# Chap-11-3.net
KiCad netlist of a schematic drawn in Altium Designer
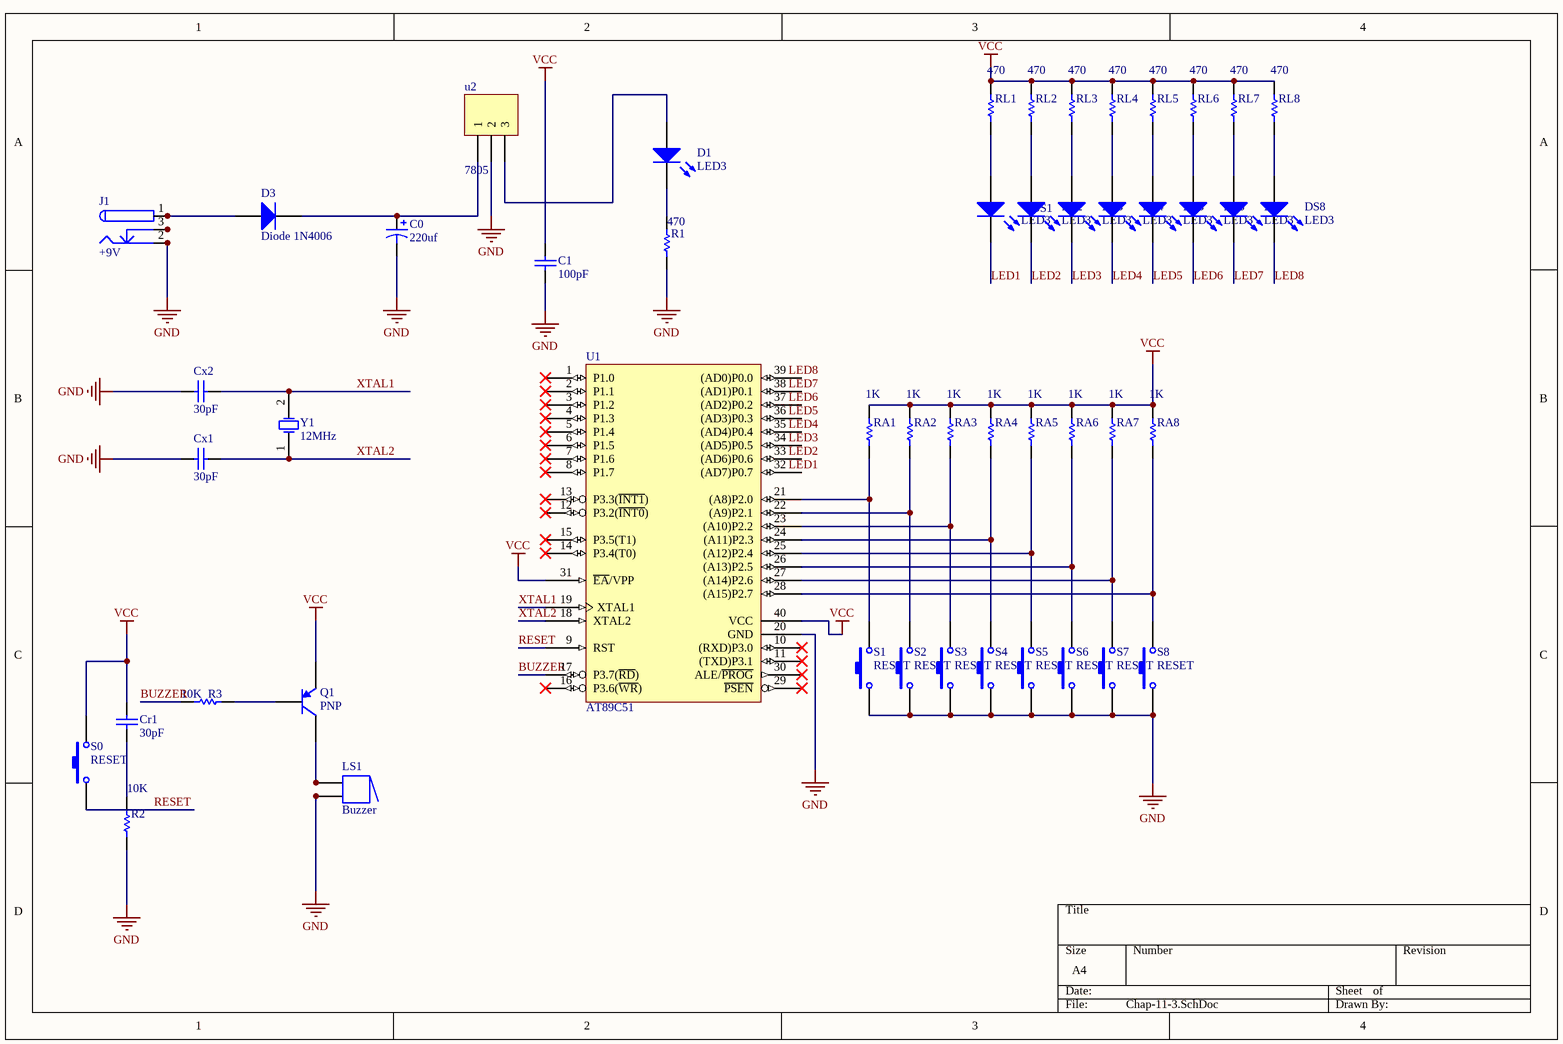
[diagram p0: Chap-11-3.SchDoc]

(export (version "E")
  (design (tool "Eeschema 10.0.6"))
  (components
    (comp (ref "C0")
      (value "220uf")
      (footprint "RB7.6-15")
      (description "Polarized Capacitor (Radial)")
      (fields (field (name "Comment") "Cap Pol1") (field (name "PUBLISHER") "Altium Limited"))
      (libsource (lib "Chap-11-实践题(3)") (part "Cap Pol1"))
    )
    (comp (ref "C1")
      (value "100pF")
      (footprint "RAD-0.3")
      (description "Capacitor")
      (fields (field (name "Comment") "Cap") (field (name "PUBLISHER") "Altium Limited"))
      (libsource (lib "Chap-11-实践题(3)") (part "Cap"))
    )
    (comp (ref "Cr1")
      (value "30pF")
      (footprint "RAD-0.3")
      (description "Capacitor")
      (fields (field (name "Comment") "Cap") (field (name "PUBLISHER") "Altium Limited"))
      (libsource (lib "Chap-11-实践题(3)") (part "Cap"))
    )
    (comp (ref "Cx1")
      (value "30pF")
      (footprint "RAD-0.3")
      (description "Capacitor")
      (fields (field (name "Comment") "Cap") (field (name "PUBLISHER") "Altium Limited"))
      (libsource (lib "Chap-11-实践题(3)") (part "Cap"))
    )
    (comp (ref "Cx2")
      (value "30pF")
      (footprint "RAD-0.3")
      (description "Capacitor")
      (fields (field (name "Comment") "Cap") (field (name "PUBLISHER") "Altium Limited"))
      (libsource (lib "Chap-11-实践题(3)") (part "Cap"))
    )
    (comp (ref "D1")
      (value "LED3")
      (footprint "3.5X2.8X1.9")
      (description "Typical BLUE SiC LED")
      (fields (field (name "PUBLISHER") "Altium Limited"))
      (libsource (lib "Chap-11-实践题(3)") (part "LED3"))
    )
    (comp (ref "D3")
      (value "Diode 1N4006")
      (footprint "DO-41")
      (description "1 Amp General Purpose Rectifier")
      (fields (field (name "PUBLISHER") "Altium Limited"))
      (libsource (lib "Chap-11-实践题(3)") (part "Diode 1N4006"))
    )
    (comp (ref "DS1")
      (value "LED3")
      (footprint "3.5X2.8X1.9")
      (description "Typical BLUE SiC LED")
      (fields (field (name "PUBLISHER") "Altium Limited"))
      (libsource (lib "Chap-11-实践题(3)") (part "LED3"))
    )
    (comp (ref "DS2")
      (value "LED3")
      (footprint "3.5X2.8X1.9")
      (description "Typical BLUE SiC LED")
      (fields (field (name "PUBLISHER") "Altium Limited"))
      (libsource (lib "Chap-11-实践题(3)") (part "LED3"))
    )
    (comp (ref "DS3")
      (value "LED3")
      (footprint "3.5X2.8X1.9")
      (description "Typical BLUE SiC LED")
      (fields (field (name "PUBLISHER") "Altium Limited"))
      (libsource (lib "Chap-11-实践题(3)") (part "LED3"))
    )
    (comp (ref "DS4")
      (value "LED3")
      (footprint "3.5X2.8X1.9")
      (description "Typical BLUE SiC LED")
      (fields (field (name "PUBLISHER") "Altium Limited"))
      (libsource (lib "Chap-11-实践题(3)") (part "LED3"))
    )
    (comp (ref "DS5")
      (value "LED3")
      (footprint "3.5X2.8X1.9")
      (description "Typical BLUE SiC LED")
      (fields (field (name "PUBLISHER") "Altium Limited"))
      (libsource (lib "Chap-11-实践题(3)") (part "LED3"))
    )
    (comp (ref "DS6")
      (value "LED3")
      (footprint "3.5X2.8X1.9")
      (description "Typical BLUE SiC LED")
      (fields (field (name "PUBLISHER") "Altium Limited"))
      (libsource (lib "Chap-11-实践题(3)") (part "LED3"))
    )
    (comp (ref "DS7")
      (value "LED3")
      (footprint "3.5X2.8X1.9")
      (description "Typical BLUE SiC LED")
      (fields (field (name "PUBLISHER") "Altium Limited"))
      (libsource (lib "Chap-11-实践题(3)") (part "LED3"))
    )
    (comp (ref "DS8")
      (value "LED3")
      (footprint "3.5X2.8X1.9")
      (description "Typical BLUE SiC LED")
      (fields (field (name "PUBLISHER") "Altium Limited"))
      (libsource (lib "Chap-11-实践题(3)") (part "LED3"))
    )
    (comp (ref "J1")
      (value "+9V")
      (footprint "KLD-0202")
      (description "Low Voltage Power Supply Connector")
      (fields (field (name "PUBLISHER") "Altium Limited"))
      (libsource (lib "Chap-11-实践题(3)") (part "PWR2.5"))
    )
    (comp (ref "LS1")
      (value "Buzzer")
      (footprint "ABSM-1574")
      (description "Magnetic Transducer Buzzer")
      (fields (field (name "PUBLISHER") "Altium Limited"))
      (libsource (lib "Chap-11-实践题(3)") (part "Buzzer"))
    )
    (comp (ref "Q1")
      (value "PNP")
      (footprint "TO-92A")
      (description "PNP General Purpose Amplifier")
      (fields (field (name "PUBLISHER") "Altium Limited"))
      (libsource (lib "Chap-11-实践题(3)") (part "2N3906"))
    )
    (comp (ref "R1")
      (value "470")
      (footprint "AXIAL-0.3")
      (description "Resistor")
      (fields (field (name "Comment") "Res1") (field (name "PUBLISHER") "Altium Limited"))
      (libsource (lib "Chap-11-实践题(3)") (part "Res1"))
    )
    (comp (ref "R2")
      (value "10K")
      (footprint "AXIAL-0.3")
      (description "Resistor")
      (fields (field (name "Comment") "Res1") (field (name "PUBLISHER") "Altium Limited"))
      (libsource (lib "Chap-11-实践题(3)") (part "Res1"))
    )
    (comp (ref "R3")
      (value "10K")
      (footprint "AXIAL-0.3")
      (description "Resistor")
      (fields (field (name "Comment") "Res1") (field (name "PUBLISHER") "Altium Limited"))
      (libsource (lib "Chap-11-实践题(3)") (part "Res1"))
    )
    (comp (ref "RA1")
      (value "1K")
      (footprint "AXIAL-0.3")
      (description "Resistor")
      (fields (field (name "Comment") "Res1") (field (name "PUBLISHER") "Altium Limited"))
      (libsource (lib "Chap-11-实践题(3)") (part "Res1"))
    )
    (comp (ref "RA2")
      (value "1K")
      (footprint "AXIAL-0.3")
      (description "Resistor")
      (fields (field (name "Comment") "Res1") (field (name "PUBLISHER") "Altium Limited"))
      (libsource (lib "Chap-11-实践题(3)") (part "Res1"))
    )
    (comp (ref "RA3")
      (value "1K")
      (footprint "AXIAL-0.3")
      (description "Resistor")
      (fields (field (name "Comment") "Res1") (field (name "PUBLISHER") "Altium Limited"))
      (libsource (lib "Chap-11-实践题(3)") (part "Res1"))
    )
    (comp (ref "RA4")
      (value "1K")
      (footprint "AXIAL-0.3")
      (description "Resistor")
      (fields (field (name "Comment") "Res1") (field (name "PUBLISHER") "Altium Limited"))
      (libsource (lib "Chap-11-实践题(3)") (part "Res1"))
    )
    (comp (ref "RA5")
      (value "1K")
      (footprint "AXIAL-0.3")
      (description "Resistor")
      (fields (field (name "Comment") "Res1") (field (name "PUBLISHER") "Altium Limited"))
      (libsource (lib "Chap-11-实践题(3)") (part "Res1"))
    )
    (comp (ref "RA6")
      (value "1K")
      (footprint "AXIAL-0.3")
      (description "Resistor")
      (fields (field (name "Comment") "Res1") (field (name "PUBLISHER") "Altium Limited"))
      (libsource (lib "Chap-11-实践题(3)") (part "Res1"))
    )
    (comp (ref "RA7")
      (value "1K")
      (footprint "AXIAL-0.3")
      (description "Resistor")
      (fields (field (name "Comment") "Res1") (field (name "PUBLISHER") "Altium Limited"))
      (libsource (lib "Chap-11-实践题(3)") (part "Res1"))
    )
    (comp (ref "RA8")
      (value "1K")
      (footprint "AXIAL-0.3")
      (description "Resistor")
      (fields (field (name "Comment") "Res1") (field (name "PUBLISHER") "Altium Limited"))
      (libsource (lib "Chap-11-实践题(3)") (part "Res1"))
    )
    (comp (ref "RL1")
      (value "470")
      (footprint "AXIAL-0.3")
      (description "Resistor")
      (fields (field (name "Comment") "Res1") (field (name "PUBLISHER") "Altium Limited"))
      (libsource (lib "Chap-11-实践题(3)") (part "Res1"))
    )
    (comp (ref "RL2")
      (value "470")
      (footprint "AXIAL-0.3")
      (description "Resistor")
      (fields (field (name "Comment") "Res1") (field (name "PUBLISHER") "Altium Limited"))
      (libsource (lib "Chap-11-实践题(3)") (part "Res1"))
    )
    (comp (ref "RL3")
      (value "470")
      (footprint "AXIAL-0.3")
      (description "Resistor")
      (fields (field (name "Comment") "Res1") (field (name "PUBLISHER") "Altium Limited"))
      (libsource (lib "Chap-11-实践题(3)") (part "Res1"))
    )
    (comp (ref "RL4")
      (value "470")
      (footprint "AXIAL-0.3")
      (description "Resistor")
      (fields (field (name "Comment") "Res1") (field (name "PUBLISHER") "Altium Limited"))
      (libsource (lib "Chap-11-实践题(3)") (part "Res1"))
    )
    (comp (ref "RL5")
      (value "470")
      (footprint "AXIAL-0.3")
      (description "Resistor")
      (fields (field (name "Comment") "Res1") (field (name "PUBLISHER") "Altium Limited"))
      (libsource (lib "Chap-11-实践题(3)") (part "Res1"))
    )
    (comp (ref "RL6")
      (value "470")
      (footprint "AXIAL-0.3")
      (description "Resistor")
      (fields (field (name "Comment") "Res1") (field (name "PUBLISHER") "Altium Limited"))
      (libsource (lib "Chap-11-实践题(3)") (part "Res1"))
    )
    (comp (ref "RL7")
      (value "470")
      (footprint "AXIAL-0.3")
      (description "Resistor")
      (fields (field (name "Comment") "Res1") (field (name "PUBLISHER") "Altium Limited"))
      (libsource (lib "Chap-11-实践题(3)") (part "Res1"))
    )
    (comp (ref "RL8")
      (value "470")
      (footprint "AXIAL-0.3")
      (description "Resistor")
      (fields (field (name "Comment") "Res1") (field (name "PUBLISHER") "Altium Limited"))
      (libsource (lib "Chap-11-实践题(3)") (part "Res1"))
    )
    (comp (ref "S0")
      (value "RESET")
      (footprint "SPST-2")
      (description "Switch")
      (fields (field (name "PUBLISHER") "Altium Limited"))
      (libsource (lib "Chap-11-实践题(3)") (part "SW-PB"))
    )
    (comp (ref "S1")
      (value "RESET")
      (footprint "SPST-2")
      (description "Switch")
      (fields (field (name "PUBLISHER") "Altium Limited"))
      (libsource (lib "Chap-11-实践题(3)") (part "SW-PB"))
    )
    (comp (ref "S2")
      (value "RESET")
      (footprint "SPST-2")
      (description "Switch")
      (fields (field (name "PUBLISHER") "Altium Limited"))
      (libsource (lib "Chap-11-实践题(3)") (part "SW-PB"))
    )
    (comp (ref "S3")
      (value "RESET")
      (footprint "SPST-2")
      (description "Switch")
      (fields (field (name "PUBLISHER") "Altium Limited"))
      (libsource (lib "Chap-11-实践题(3)") (part "SW-PB"))
    )
    (comp (ref "S4")
      (value "RESET")
      (footprint "SPST-2")
      (description "Switch")
      (fields (field (name "PUBLISHER") "Altium Limited"))
      (libsource (lib "Chap-11-实践题(3)") (part "SW-PB"))
    )
    (comp (ref "S5")
      (value "RESET")
      (footprint "SPST-2")
      (description "Switch")
      (fields (field (name "PUBLISHER") "Altium Limited"))
      (libsource (lib "Chap-11-实践题(3)") (part "SW-PB"))
    )
    (comp (ref "S6")
      (value "RESET")
      (footprint "SPST-2")
      (description "Switch")
      (fields (field (name "PUBLISHER") "Altium Limited"))
      (libsource (lib "Chap-11-实践题(3)") (part "SW-PB"))
    )
    (comp (ref "S7")
      (value "RESET")
      (footprint "SPST-2")
      (description "Switch")
      (fields (field (name "PUBLISHER") "Altium Limited"))
      (libsource (lib "Chap-11-实践题(3)") (part "SW-PB"))
    )
    (comp (ref "S8")
      (value "RESET")
      (footprint "SPST-2")
      (description "Switch")
      (fields (field (name "PUBLISHER") "Altium Limited"))
      (libsource (lib "Chap-11-实践题(3)") (part "SW-PB"))
    )
    (comp (ref "U1")
      (value "AT89C51")
      (footprint "DIP-40")
      (description "8-Bit Microcontroller with 4K Flash ROM")
      (libsource (lib "Chap-11-实践题(3)") (part "AT89C51"))
    )
    (comp (ref "u2")
      (value "7805")
      (footprint "HDR1X3H")
      (description "Header, 3-Pin, Right Angle")
      (fields (field (name "PUBLISHER") "Altium Limited"))
      (libsource (lib "Chap-11-实践题(3)") (part "Header 3H"))
    )
    (comp (ref "Y1")
      (value "12MHz")
      (footprint "R38")
      (description "Crystal Oscillator")
      (fields (field (name "PUBLISHER") "Altium Limited"))
      (libsource (lib "Chap-11-实践题(3)") (part "XTAL"))
    )
  )
  (nets
    (net (code "1") (name "/BUZZER") (class "Default")
      (node (ref "R3") (pin "1") (pinfunction "1_1") (pintype "passive"))
      (node (ref "U1") (pin "17") (pinfunction "P3.7(~{RD})_17") (pintype "bidirectional"))
    )
    (net (code "2") (name "/LED1") (class "Default")
      (node (ref "DS1") (pin "2") (pinfunction "K_2") (pintype "passive"))
    )
    (net (code "3") (name "/LED2") (class "Default")
      (node (ref "DS2") (pin "2") (pinfunction "K_2") (pintype "passive"))
    )
    (net (code "4") (name "/LED3") (class "Default")
      (node (ref "DS3") (pin "2") (pinfunction "K_2") (pintype "passive"))
    )
    (net (code "5") (name "/LED4") (class "Default")
      (node (ref "DS4") (pin "2") (pinfunction "K_2") (pintype "passive"))
    )
    (net (code "6") (name "/LED5") (class "Default")
      (node (ref "DS5") (pin "2") (pinfunction "K_2") (pintype "passive"))
    )
    (net (code "7") (name "/LED6") (class "Default")
      (node (ref "DS6") (pin "2") (pinfunction "K_2") (pintype "passive"))
    )
    (net (code "8") (name "/LED7") (class "Default")
      (node (ref "DS7") (pin "2") (pinfunction "K_2") (pintype "passive"))
    )
    (net (code "9") (name "/LED8") (class "Default")
      (node (ref "DS8") (pin "2") (pinfunction "K_2") (pintype "passive"))
    )
    (net (code "10") (name "/RESET") (class "Default")
      (node (ref "S0") (pin "1") (pinfunction "1_1") (pintype "passive"))
      (node (ref "U1") (pin "9") (pinfunction "RST_9") (pintype "input"))
    )
    (net (code "11") (name "/XTAL1") (class "Default")
      (node (ref "Cx2") (pin "1") (pinfunction "1_1") (pintype "passive"))
      (node (ref "U1") (pin "19") (pinfunction "XTAL1_19") (pintype "input"))
      (node (ref "Y1") (pin "2") (pinfunction "OSC2_2") (pintype "passive"))
    )
    (net (code "12") (name "/XTAL2") (class "Default")
      (node (ref "Cx1") (pin "1") (pinfunction "1_1") (pintype "passive"))
      (node (ref "U1") (pin "18") (pinfunction "XTAL2_18") (pintype "input"))
      (node (ref "Y1") (pin "1") (pinfunction "OSC1_1") (pintype "passive"))
    )
    (net (code "13") (name "GND") (class "Default")
      (node (ref "C0") (pin "2") (pinfunction "2_2") (pintype "passive"))
      (node (ref "C1") (pin "1") (pinfunction "1_1") (pintype "passive"))
      (node (ref "Cx1") (pin "2") (pinfunction "2_2") (pintype "passive"))
      (node (ref "Cx2") (pin "2") (pinfunction "2_2") (pintype "passive"))
      (node (ref "J1") (pin "2") (pinfunction "2_2") (pintype "power_in"))
      (node (ref "J1") (pin "2A") (pinfunction "2A_2A") (pintype "power_in"))
      (node (ref "J1") (pin "2B") (pinfunction "2B_2B") (pintype "power_in"))
      (node (ref "LS1") (pin "2") (pinfunction "2_2") (pintype "passive"))
      (node (ref "LS1") (pin "2A") (pinfunction "2A_2A") (pintype "passive"))
      (node (ref "R1") (pin "1") (pinfunction "1_1") (pintype "passive"))
      (node (ref "R2") (pin "1") (pinfunction "1_1") (pintype "passive"))
      (node (ref "S1") (pin "1") (pinfunction "1_1") (pintype "passive"))
      (node (ref "S2") (pin "1") (pinfunction "1_1") (pintype "passive"))
      (node (ref "S3") (pin "1") (pinfunction "1_1") (pintype "passive"))
      (node (ref "S4") (pin "1") (pinfunction "1_1") (pintype "passive"))
      (node (ref "S5") (pin "1") (pinfunction "1_1") (pintype "passive"))
      (node (ref "S6") (pin "1") (pinfunction "1_1") (pintype "passive"))
      (node (ref "S7") (pin "1") (pinfunction "1_1") (pintype "passive"))
      (node (ref "S8") (pin "1") (pinfunction "1_1") (pintype "passive"))
      (node (ref "U1") (pin "20") (pinfunction "GND_20") (pintype "power_in"))
      (node (ref "u2") (pin "2") (pinfunction "2_2") (pintype "passive"))
    )
    (net (code "14") (name "Net-(Cr1-Pad1)") (class "Default")
      (node (ref "Cr1") (pin "1") (pinfunction "1_1") (pintype "passive"))
      (node (ref "R2") (pin "2") (pinfunction "2_2") (pintype "passive"))
    )
    (net (code "15") (name "Net-(D1-A)") (class "Default")
      (node (ref "D1") (pin "1") (pinfunction "A_1") (pintype "passive"))
      (node (ref "u2") (pin "3") (pinfunction "3_3") (pintype "passive"))
    )
    (net (code "16") (name "Net-(D1-K)") (class "Default")
      (node (ref "D1") (pin "2") (pinfunction "K_2") (pintype "passive"))
      (node (ref "R1") (pin "2") (pinfunction "2_2") (pintype "passive"))
    )
    (net (code "17") (name "Net-(D3-A)") (class "Default")
      (node (ref "D3") (pin "1") (pinfunction "A_1") (pintype "passive"))
      (node (ref "J1") (pin "1") (pinfunction "1_1") (pintype "power_in"))
      (node (ref "J1") (pin "1A") (pinfunction "1A_1A") (pintype "power_in"))
      (node (ref "J1") (pin "1B") (pinfunction "1B_1B") (pintype "power_in"))
    )
    (net (code "18") (name "Net-(D3-K)") (class "Default")
      (node (ref "C0") (pin "1") (pinfunction "1_1") (pintype "passive"))
      (node (ref "D3") (pin "2") (pinfunction "K_2") (pintype "passive"))
      (node (ref "u2") (pin "1") (pinfunction "1_1") (pintype "passive"))
    )
    (net (code "19") (name "Net-(DS1-A)") (class "Default")
      (node (ref "DS1") (pin "1") (pinfunction "A_1") (pintype "passive"))
      (node (ref "RL1") (pin "1") (pinfunction "1_1") (pintype "passive"))
    )
    (net (code "20") (name "Net-(DS2-A)") (class "Default")
      (node (ref "DS2") (pin "1") (pinfunction "A_1") (pintype "passive"))
      (node (ref "RL2") (pin "1") (pinfunction "1_1") (pintype "passive"))
    )
    (net (code "21") (name "Net-(DS3-A)") (class "Default")
      (node (ref "DS3") (pin "1") (pinfunction "A_1") (pintype "passive"))
      (node (ref "RL3") (pin "1") (pinfunction "1_1") (pintype "passive"))
    )
    (net (code "22") (name "Net-(DS4-A)") (class "Default")
      (node (ref "DS4") (pin "1") (pinfunction "A_1") (pintype "passive"))
      (node (ref "RL4") (pin "1") (pinfunction "1_1") (pintype "passive"))
    )
    (net (code "23") (name "Net-(DS5-A)") (class "Default")
      (node (ref "DS5") (pin "1") (pinfunction "A_1") (pintype "passive"))
      (node (ref "RL5") (pin "1") (pinfunction "1_1") (pintype "passive"))
    )
    (net (code "24") (name "Net-(DS6-A)") (class "Default")
      (node (ref "DS6") (pin "1") (pinfunction "A_1") (pintype "passive"))
      (node (ref "RL6") (pin "1") (pinfunction "1_1") (pintype "passive"))
    )
    (net (code "25") (name "Net-(DS7-A)") (class "Default")
      (node (ref "DS7") (pin "1") (pinfunction "A_1") (pintype "passive"))
      (node (ref "RL7") (pin "1") (pinfunction "1_1") (pintype "passive"))
    )
    (net (code "26") (name "Net-(DS8-A)") (class "Default")
      (node (ref "DS8") (pin "1") (pinfunction "A_1") (pintype "passive"))
      (node (ref "RL8") (pin "1") (pinfunction "1_1") (pintype "passive"))
    )
    (net (code "27") (name "Net-(J1-Pad3)") (class "Default")
      (node (ref "J1") (pin "3") (pinfunction "3_3") (pintype "power_in"))
      (node (ref "J1") (pin "3A") (pinfunction "3A_3A") (pintype "power_in"))
      (node (ref "J1") (pin "3B") (pinfunction "3B_3B") (pintype "power_in"))
    )
    (net (code "28") (name "Net-(Q1-B)") (class "Default")
      (node (ref "Q1") (pin "2") (pinfunction "B_2") (pintype "passive"))
      (node (ref "R3") (pin "2") (pinfunction "2_2") (pintype "passive"))
    )
    (net (code "29") (name "Net-(Q1-C)") (class "Default")
      (node (ref "LS1") (pin "1") (pinfunction "1_1") (pintype "passive"))
      (node (ref "LS1") (pin "1A") (pinfunction "1A_1A") (pintype "passive"))
      (node (ref "Q1") (pin "3") (pinfunction "C_3") (pintype "passive"))
    )
    (net (code "30") (name "Net-(U1-(A8)P2.0)") (class "Default")
      (node (ref "RA1") (pin "1") (pinfunction "1_1") (pintype "passive"))
      (node (ref "S1") (pin "2") (pinfunction "2_2") (pintype "passive"))
      (node (ref "U1") (pin "21") (pinfunction "(A8)P2.0_21") (pintype "bidirectional"))
    )
    (net (code "31") (name "Net-(U1-(A9)P2.1)") (class "Default")
      (node (ref "RA2") (pin "1") (pinfunction "1_1") (pintype "passive"))
      (node (ref "S2") (pin "2") (pinfunction "2_2") (pintype "passive"))
      (node (ref "U1") (pin "22") (pinfunction "(A9)P2.1_22") (pintype "bidirectional"))
    )
    (net (code "32") (name "Net-(U1-(A10)P2.2)") (class "Default")
      (node (ref "RA3") (pin "1") (pinfunction "1_1") (pintype "passive"))
      (node (ref "S3") (pin "2") (pinfunction "2_2") (pintype "passive"))
      (node (ref "U1") (pin "23") (pinfunction "(A10)P2.2_23") (pintype "bidirectional"))
    )
    (net (code "33") (name "Net-(U1-(A11)P2.3)") (class "Default")
      (node (ref "RA4") (pin "1") (pinfunction "1_1") (pintype "passive"))
      (node (ref "S4") (pin "2") (pinfunction "2_2") (pintype "passive"))
      (node (ref "U1") (pin "24") (pinfunction "(A11)P2.3_24") (pintype "bidirectional"))
    )
    (net (code "34") (name "Net-(U1-(A12)P2.4)") (class "Default")
      (node (ref "RA5") (pin "1") (pinfunction "1_1") (pintype "passive"))
      (node (ref "S5") (pin "2") (pinfunction "2_2") (pintype "passive"))
      (node (ref "U1") (pin "25") (pinfunction "(A12)P2.4_25") (pintype "bidirectional"))
    )
    (net (code "35") (name "Net-(U1-(A13)P2.5)") (class "Default")
      (node (ref "RA6") (pin "1") (pinfunction "1_1") (pintype "passive"))
      (node (ref "S6") (pin "2") (pinfunction "2_2") (pintype "passive"))
      (node (ref "U1") (pin "26") (pinfunction "(A13)P2.5_26") (pintype "bidirectional"))
    )
    (net (code "36") (name "Net-(U1-(A14)P2.6)") (class "Default")
      (node (ref "RA7") (pin "1") (pinfunction "1_1") (pintype "passive"))
      (node (ref "S7") (pin "2") (pinfunction "2_2") (pintype "passive"))
      (node (ref "U1") (pin "27") (pinfunction "(A14)P2.6_27") (pintype "bidirectional"))
    )
    (net (code "37") (name "Net-(U1-(A15)P2.7)") (class "Default")
      (node (ref "RA8") (pin "1") (pinfunction "1_1") (pintype "passive"))
      (node (ref "S8") (pin "2") (pinfunction "2_2") (pintype "passive"))
      (node (ref "U1") (pin "28") (pinfunction "(A15)P2.7_28") (pintype "bidirectional"))
    )
    (net (code "38") (name "VCC") (class "Default")
      (node (ref "C1") (pin "2") (pinfunction "2_2") (pintype "passive"))
      (node (ref "Cr1") (pin "2") (pinfunction "2_2") (pintype "passive"))
      (node (ref "Q1") (pin "1") (pinfunction "E_1") (pintype "passive"))
      (node (ref "RA1") (pin "2") (pinfunction "2_2") (pintype "passive"))
      (node (ref "RA2") (pin "2") (pinfunction "2_2") (pintype "passive"))
      (node (ref "RA3") (pin "2") (pinfunction "2_2") (pintype "passive"))
      (node (ref "RA4") (pin "2") (pinfunction "2_2") (pintype "passive"))
      (node (ref "RA5") (pin "2") (pinfunction "2_2") (pintype "passive"))
      (node (ref "RA6") (pin "2") (pinfunction "2_2") (pintype "passive"))
      (node (ref "RA7") (pin "2") (pinfunction "2_2") (pintype "passive"))
      (node (ref "RA8") (pin "2") (pinfunction "2_2") (pintype "passive"))
      (node (ref "RL1") (pin "2") (pinfunction "2_2") (pintype "passive"))
      (node (ref "RL2") (pin "2") (pinfunction "2_2") (pintype "passive"))
      (node (ref "RL3") (pin "2") (pinfunction "2_2") (pintype "passive"))
      (node (ref "RL4") (pin "2") (pinfunction "2_2") (pintype "passive"))
      (node (ref "RL5") (pin "2") (pinfunction "2_2") (pintype "passive"))
      (node (ref "RL6") (pin "2") (pinfunction "2_2") (pintype "passive"))
      (node (ref "RL7") (pin "2") (pinfunction "2_2") (pintype "passive"))
      (node (ref "RL8") (pin "2") (pinfunction "2_2") (pintype "passive"))
      (node (ref "S0") (pin "2") (pinfunction "2_2") (pintype "passive"))
      (node (ref "U1") (pin "31") (pinfunction "~{EA}/VPP_31") (pintype "input"))
      (node (ref "U1") (pin "40") (pinfunction "VCC_40") (pintype "power_in"))
    )
    (net (code "39") (name "unconnected-(U1-(AD0)P0.0-Pad39)") (class "Default")
      (node (ref "U1") (pin "39") (pinfunction "(AD0)P0.0_39") (pintype "bidirectional"))
    )
    (net (code "40") (name "unconnected-(U1-(AD1)P0.1-Pad38)") (class "Default")
      (node (ref "U1") (pin "38") (pinfunction "(AD1)P0.1_38") (pintype "bidirectional"))
    )
    (net (code "41") (name "unconnected-(U1-(AD2)P0.2-Pad37)") (class "Default")
      (node (ref "U1") (pin "37") (pinfunction "(AD2)P0.2_37") (pintype "bidirectional"))
    )
    (net (code "42") (name "unconnected-(U1-(AD3)P0.3-Pad36)") (class "Default")
      (node (ref "U1") (pin "36") (pinfunction "(AD3)P0.3_36") (pintype "bidirectional"))
    )
    (net (code "43") (name "unconnected-(U1-(AD4)P0.4-Pad35)") (class "Default")
      (node (ref "U1") (pin "35") (pinfunction "(AD4)P0.4_35") (pintype "bidirectional"))
    )
    (net (code "44") (name "unconnected-(U1-(AD5)P0.5-Pad34)") (class "Default")
      (node (ref "U1") (pin "34") (pinfunction "(AD5)P0.5_34") (pintype "bidirectional"))
    )
    (net (code "45") (name "unconnected-(U1-(AD6)P0.6-Pad33)") (class "Default")
      (node (ref "U1") (pin "33") (pinfunction "(AD6)P0.6_33") (pintype "bidirectional"))
    )
    (net (code "46") (name "unconnected-(U1-(AD7)P0.7-Pad32)") (class "Default")
      (node (ref "U1") (pin "32") (pinfunction "(AD7)P0.7_32") (pintype "bidirectional"))
    )
    (net (code "47") (name "unconnected-(U1-(RXD)P3.0-Pad10)") (class "Default")
      (node (ref "U1") (pin "10") (pinfunction "(RXD)P3.0_10") (pintype "bidirectional+no_connect"))
    )
    (net (code "48") (name "unconnected-(U1-(TXD)P3.1-Pad11)") (class "Default")
      (node (ref "U1") (pin "11") (pinfunction "(TXD)P3.1_11") (pintype "bidirectional+no_connect"))
    )
    (net (code "49") (name "unconnected-(U1-ALE{slash}~{PROG}-Pad30)") (class "Default")
      (node (ref "U1") (pin "30") (pinfunction "ALE/~{PROG}_30") (pintype "output+no_connect"))
    )
    (net (code "50") (name "unconnected-(U1-P1.0-Pad1)") (class "Default")
      (node (ref "U1") (pin "1") (pinfunction "P1.0_1") (pintype "bidirectional+no_connect"))
    )
    (net (code "51") (name "unconnected-(U1-P1.1-Pad2)") (class "Default")
      (node (ref "U1") (pin "2") (pinfunction "P1.1_2") (pintype "bidirectional+no_connect"))
    )
    (net (code "52") (name "unconnected-(U1-P1.2-Pad3)") (class "Default")
      (node (ref "U1") (pin "3") (pinfunction "P1.2_3") (pintype "bidirectional+no_connect"))
    )
    (net (code "53") (name "unconnected-(U1-P1.3-Pad4)") (class "Default")
      (node (ref "U1") (pin "4") (pinfunction "P1.3_4") (pintype "bidirectional+no_connect"))
    )
    (net (code "54") (name "unconnected-(U1-P1.4-Pad5)") (class "Default")
      (node (ref "U1") (pin "5") (pinfunction "P1.4_5") (pintype "bidirectional+no_connect"))
    )
    (net (code "55") (name "unconnected-(U1-P1.5-Pad6)") (class "Default")
      (node (ref "U1") (pin "6") (pinfunction "P1.5_6") (pintype "bidirectional+no_connect"))
    )
    (net (code "56") (name "unconnected-(U1-P1.6-Pad7)") (class "Default")
      (node (ref "U1") (pin "7") (pinfunction "P1.6_7") (pintype "bidirectional+no_connect"))
    )
    (net (code "57") (name "unconnected-(U1-P1.7-Pad8)") (class "Default")
      (node (ref "U1") (pin "8") (pinfunction "P1.7_8") (pintype "bidirectional+no_connect"))
    )
    (net (code "58") (name "unconnected-(U1-P3.2(~{INT0})-Pad12)") (class "Default")
      (node (ref "U1") (pin "12") (pinfunction "P3.2(~{INT0})_12") (pintype "bidirectional+no_connect"))
    )
    (net (code "59") (name "unconnected-(U1-P3.3(~{INT1})-Pad13)") (class "Default")
      (node (ref "U1") (pin "13") (pinfunction "P3.3(~{INT1})_13") (pintype "bidirectional+no_connect"))
    )
    (net (code "60") (name "unconnected-(U1-P3.4(T0)-Pad14)") (class "Default")
      (node (ref "U1") (pin "14") (pinfunction "P3.4(T0)_14") (pintype "bidirectional+no_connect"))
    )
    (net (code "61") (name "unconnected-(U1-P3.5(T1)-Pad15)") (class "Default")
      (node (ref "U1") (pin "15") (pinfunction "P3.5(T1)_15") (pintype "bidirectional+no_connect"))
    )
    (net (code "62") (name "unconnected-(U1-P3.6(~{WR})-Pad16)") (class "Default")
      (node (ref "U1") (pin "16") (pinfunction "P3.6(~{WR})_16") (pintype "bidirectional+no_connect"))
    )
    (net (code "63") (name "unconnected-(U1-~{PSEN}-Pad29)") (class "Default")
      (node (ref "U1") (pin "29") (pinfunction "~{PSEN}_29") (pintype "output+no_connect"))
    )
  )
)
